# Sheet1.net
KiCad netlist of a schematic drawn in Altium Designer
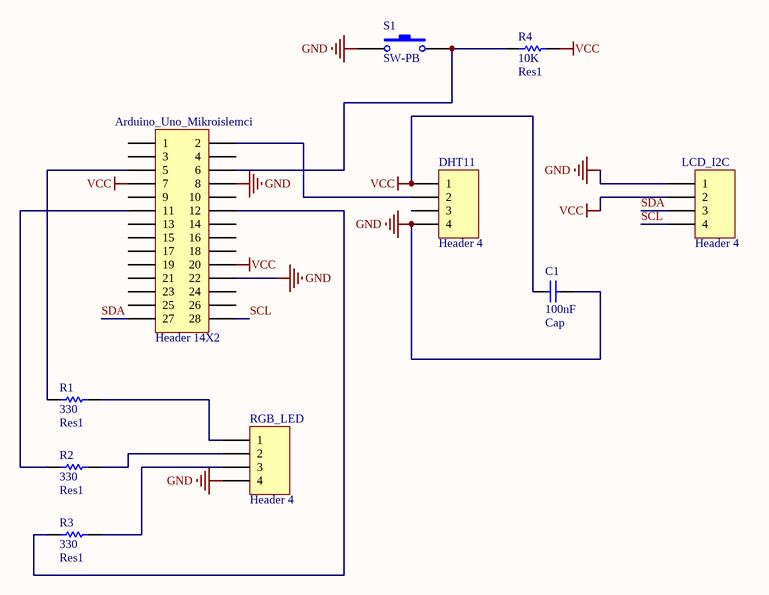
[diagram p0: Sheet1.SchDoc]

(export (version "E")
  (design (tool "Eeschema 10.0.6"))
  (components
    (comp (ref "Arduino_Uno_Mikroislemci")
      (value "Header 14X2")
      (footprint "HDR2X14")
      (description "Header, 14-Pin, Dual row")
      (fields (field (name "PUBLISHER") "Altium Limited"))
      (libsource (lib "miscellaneous_connectors") (part "Header 14X2"))
    )
    (comp (ref "C1")
      (value "Cap")
      (footprint "RAD-0.3")
      (description "Capacitor")
      (fields (field (name "ALTIUM_VALUE") "100nF") (field (name "PUBLISHER") "Altium Limited"))
      (libsource (lib "Miscellaneous Devices") (part "Cap"))
    )
    (comp (ref "DHT11")
      (value "Header 4")
      (footprint "HDR1X4")
      (description "Header, 4-Pin")
      (fields (field (name "PUBLISHER") "Altium Limited"))
      (libsource (lib "miscellaneous_connectors") (part "Header 4"))
    )
    (comp (ref "LCD_I2C")
      (value "Header 4")
      (footprint "HDR1X4")
      (description "Header, 4-Pin")
      (fields (field (name "PUBLISHER") "Altium Limited"))
      (libsource (lib "miscellaneous_connectors") (part "Header 4"))
    )
    (comp (ref "R1")
      (value "Res1")
      (footprint "AXIAL-0.3")
      (description "Resistor")
      (fields (field (name "ALTIUM_VALUE") "330") (field (name "PUBLISHER") "Altium Limited"))
      (libsource (lib "Miscellaneous Devices") (part "Res1"))
    )
    (comp (ref "R2")
      (value "Res1")
      (footprint "AXIAL-0.3")
      (description "Resistor")
      (fields (field (name "ALTIUM_VALUE") "330") (field (name "PUBLISHER") "Altium Limited"))
      (libsource (lib "Miscellaneous Devices") (part "Res1"))
    )
    (comp (ref "R3")
      (value "Res1")
      (footprint "AXIAL-0.3")
      (description "Resistor")
      (fields (field (name "ALTIUM_VALUE") "330") (field (name "PUBLISHER") "Altium Limited"))
      (libsource (lib "Miscellaneous Devices") (part "Res1"))
    )
    (comp (ref "R4")
      (value "Res1")
      (footprint "AXIAL-0.3")
      (description "Resistor")
      (fields (field (name "ALTIUM_VALUE") "10K") (field (name "PUBLISHER") "Altium Limited"))
      (libsource (lib "Miscellaneous Devices") (part "Res1"))
    )
    (comp (ref "RGB_LED")
      (value "Header 4")
      (footprint "HDR1X4")
      (description "Header, 4-Pin")
      (fields (field (name "PUBLISHER") "Altium Limited"))
      (libsource (lib "miscellaneous_connectors") (part "Header 4"))
    )
    (comp (ref "S1")
      (value "SW-PB")
      (footprint "SPST-2")
      (description "Switch")
      (fields (field (name "PUBLISHER") "Altium Limited"))
      (libsource (lib "Miscellaneous Devices") (part "SW-PB"))
    )
  )
  (nets
    (net (code "1") (name "/SCL") (class "Default")
      (node (ref "Arduino_Uno_Mikroislemci") (pin "28") (pinfunction "28_28") (pintype "passive"))
      (node (ref "LCD_I2C") (pin "4") (pinfunction "4_4") (pintype "passive"))
    )
    (net (code "2") (name "/SDA") (class "Default")
      (node (ref "Arduino_Uno_Mikroislemci") (pin "27") (pinfunction "27_27") (pintype "passive"))
      (node (ref "LCD_I2C") (pin "3") (pinfunction "3_3") (pintype "passive"))
    )
    (net (code "3") (name "GND") (class "Default")
      (node (ref "Arduino_Uno_Mikroislemci") (pin "22") (pinfunction "22_22") (pintype "passive"))
      (node (ref "Arduino_Uno_Mikroislemci") (pin "8") (pinfunction "8_8") (pintype "passive"))
      (node (ref "C1") (pin "2") (pinfunction "2_2") (pintype "passive"))
      (node (ref "DHT11") (pin "4") (pinfunction "4_4") (pintype "passive"))
      (node (ref "LCD_I2C") (pin "1") (pinfunction "1_1") (pintype "passive"))
      (node (ref "RGB_LED") (pin "4") (pinfunction "4_4") (pintype "passive"))
      (node (ref "S1") (pin "1") (pinfunction "1_1") (pintype "passive"))
    )
    (net (code "4") (name "Net-(Arduino_Uno_Mikroislemci-Pad2)") (class "Default")
      (node (ref "Arduino_Uno_Mikroislemci") (pin "2") (pinfunction "2_2") (pintype "passive"))
      (node (ref "DHT11") (pin "2") (pinfunction "2_2") (pintype "passive"))
    )
    (net (code "5") (name "Net-(Arduino_Uno_Mikroislemci-Pad5)") (class "Default")
      (node (ref "Arduino_Uno_Mikroislemci") (pin "5") (pinfunction "5_5") (pintype "passive"))
      (node (ref "R1") (pin "1") (pinfunction "1_1") (pintype "passive"))
    )
    (net (code "6") (name "Net-(Arduino_Uno_Mikroislemci-Pad6)") (class "Default")
      (node (ref "Arduino_Uno_Mikroislemci") (pin "6") (pinfunction "6_6") (pintype "passive"))
      (node (ref "R4") (pin "1") (pinfunction "1_1") (pintype "passive"))
      (node (ref "S1") (pin "2") (pinfunction "2_2") (pintype "passive"))
    )
    (net (code "7") (name "Net-(Arduino_Uno_Mikroislemci-Pad11)") (class "Default")
      (node (ref "Arduino_Uno_Mikroislemci") (pin "11") (pinfunction "11_11") (pintype "passive"))
      (node (ref "R2") (pin "1") (pinfunction "1_1") (pintype "passive"))
    )
    (net (code "8") (name "Net-(Arduino_Uno_Mikroislemci-Pad12)") (class "Default")
      (node (ref "Arduino_Uno_Mikroislemci") (pin "12") (pinfunction "12_12") (pintype "passive"))
      (node (ref "R3") (pin "1") (pinfunction "1_1") (pintype "passive"))
    )
    (net (code "9") (name "Net-(R1-Pad2)") (class "Default")
      (node (ref "R1") (pin "2") (pinfunction "2_2") (pintype "passive"))
      (node (ref "RGB_LED") (pin "1") (pinfunction "1_1") (pintype "passive"))
    )
    (net (code "10") (name "Net-(R2-Pad2)") (class "Default")
      (node (ref "R2") (pin "2") (pinfunction "2_2") (pintype "passive"))
      (node (ref "RGB_LED") (pin "2") (pinfunction "2_2") (pintype "passive"))
    )
    (net (code "11") (name "Net-(R3-Pad2)") (class "Default")
      (node (ref "R3") (pin "2") (pinfunction "2_2") (pintype "passive"))
      (node (ref "RGB_LED") (pin "3") (pinfunction "3_3") (pintype "passive"))
    )
    (net (code "12") (name "VCC") (class "Default")
      (node (ref "Arduino_Uno_Mikroislemci") (pin "20") (pinfunction "20_20") (pintype "passive"))
      (node (ref "Arduino_Uno_Mikroislemci") (pin "7") (pinfunction "7_7") (pintype "passive"))
      (node (ref "C1") (pin "1") (pinfunction "1_1") (pintype "passive"))
      (node (ref "DHT11") (pin "1") (pinfunction "1_1") (pintype "passive"))
      (node (ref "LCD_I2C") (pin "2") (pinfunction "2_2") (pintype "passive"))
      (node (ref "R4") (pin "2") (pinfunction "2_2") (pintype "passive"))
    )
    (net (code "13") (name "unconnected-(Arduino_Uno_Mikroislemci-Pad1)") (class "Default")
      (node (ref "Arduino_Uno_Mikroislemci") (pin "1") (pinfunction "1_1") (pintype "passive"))
    )
    (net (code "14") (name "unconnected-(Arduino_Uno_Mikroislemci-Pad3)") (class "Default")
      (node (ref "Arduino_Uno_Mikroislemci") (pin "3") (pinfunction "3_3") (pintype "passive"))
    )
    (net (code "15") (name "unconnected-(Arduino_Uno_Mikroislemci-Pad4)") (class "Default")
      (node (ref "Arduino_Uno_Mikroislemci") (pin "4") (pinfunction "4_4") (pintype "passive"))
    )
    (net (code "16") (name "unconnected-(Arduino_Uno_Mikroislemci-Pad9)") (class "Default")
      (node (ref "Arduino_Uno_Mikroislemci") (pin "9") (pinfunction "9_9") (pintype "passive"))
    )
    (net (code "17") (name "unconnected-(Arduino_Uno_Mikroislemci-Pad10)") (class "Default")
      (node (ref "Arduino_Uno_Mikroislemci") (pin "10") (pinfunction "10_10") (pintype "passive"))
    )
    (net (code "18") (name "unconnected-(Arduino_Uno_Mikroislemci-Pad13)") (class "Default")
      (node (ref "Arduino_Uno_Mikroislemci") (pin "13") (pinfunction "13_13") (pintype "passive"))
    )
    (net (code "19") (name "unconnected-(Arduino_Uno_Mikroislemci-Pad14)") (class "Default")
      (node (ref "Arduino_Uno_Mikroislemci") (pin "14") (pinfunction "14_14") (pintype "passive"))
    )
    (net (code "20") (name "unconnected-(Arduino_Uno_Mikroislemci-Pad15)") (class "Default")
      (node (ref "Arduino_Uno_Mikroislemci") (pin "15") (pinfunction "15_15") (pintype "passive"))
    )
    (net (code "21") (name "unconnected-(Arduino_Uno_Mikroislemci-Pad16)") (class "Default")
      (node (ref "Arduino_Uno_Mikroislemci") (pin "16") (pinfunction "16_16") (pintype "passive"))
    )
    (net (code "22") (name "unconnected-(Arduino_Uno_Mikroislemci-Pad17)") (class "Default")
      (node (ref "Arduino_Uno_Mikroislemci") (pin "17") (pinfunction "17_17") (pintype "passive"))
    )
    (net (code "23") (name "unconnected-(Arduino_Uno_Mikroislemci-Pad18)") (class "Default")
      (node (ref "Arduino_Uno_Mikroislemci") (pin "18") (pinfunction "18_18") (pintype "passive"))
    )
    (net (code "24") (name "unconnected-(Arduino_Uno_Mikroislemci-Pad19)") (class "Default")
      (node (ref "Arduino_Uno_Mikroislemci") (pin "19") (pinfunction "19_19") (pintype "passive"))
    )
    (net (code "25") (name "unconnected-(Arduino_Uno_Mikroislemci-Pad21)") (class "Default")
      (node (ref "Arduino_Uno_Mikroislemci") (pin "21") (pinfunction "21_21") (pintype "passive"))
    )
    (net (code "26") (name "unconnected-(Arduino_Uno_Mikroislemci-Pad23)") (class "Default")
      (node (ref "Arduino_Uno_Mikroislemci") (pin "23") (pinfunction "23_23") (pintype "passive"))
    )
    (net (code "27") (name "unconnected-(Arduino_Uno_Mikroislemci-Pad24)") (class "Default")
      (node (ref "Arduino_Uno_Mikroislemci") (pin "24") (pinfunction "24_24") (pintype "passive"))
    )
    (net (code "28") (name "unconnected-(Arduino_Uno_Mikroislemci-Pad25)") (class "Default")
      (node (ref "Arduino_Uno_Mikroislemci") (pin "25") (pinfunction "25_25") (pintype "passive"))
    )
    (net (code "29") (name "unconnected-(Arduino_Uno_Mikroislemci-Pad26)") (class "Default")
      (node (ref "Arduino_Uno_Mikroislemci") (pin "26") (pinfunction "26_26") (pintype "passive"))
    )
    (net (code "30") (name "unconnected-(DHT11-Pad3)") (class "Default")
      (node (ref "DHT11") (pin "3") (pinfunction "3_3") (pintype "passive"))
    )
  )
)
